# Ada_-_V2_as_built.net
KiCad netlist of a schematic drawn in EasyEDA Pro
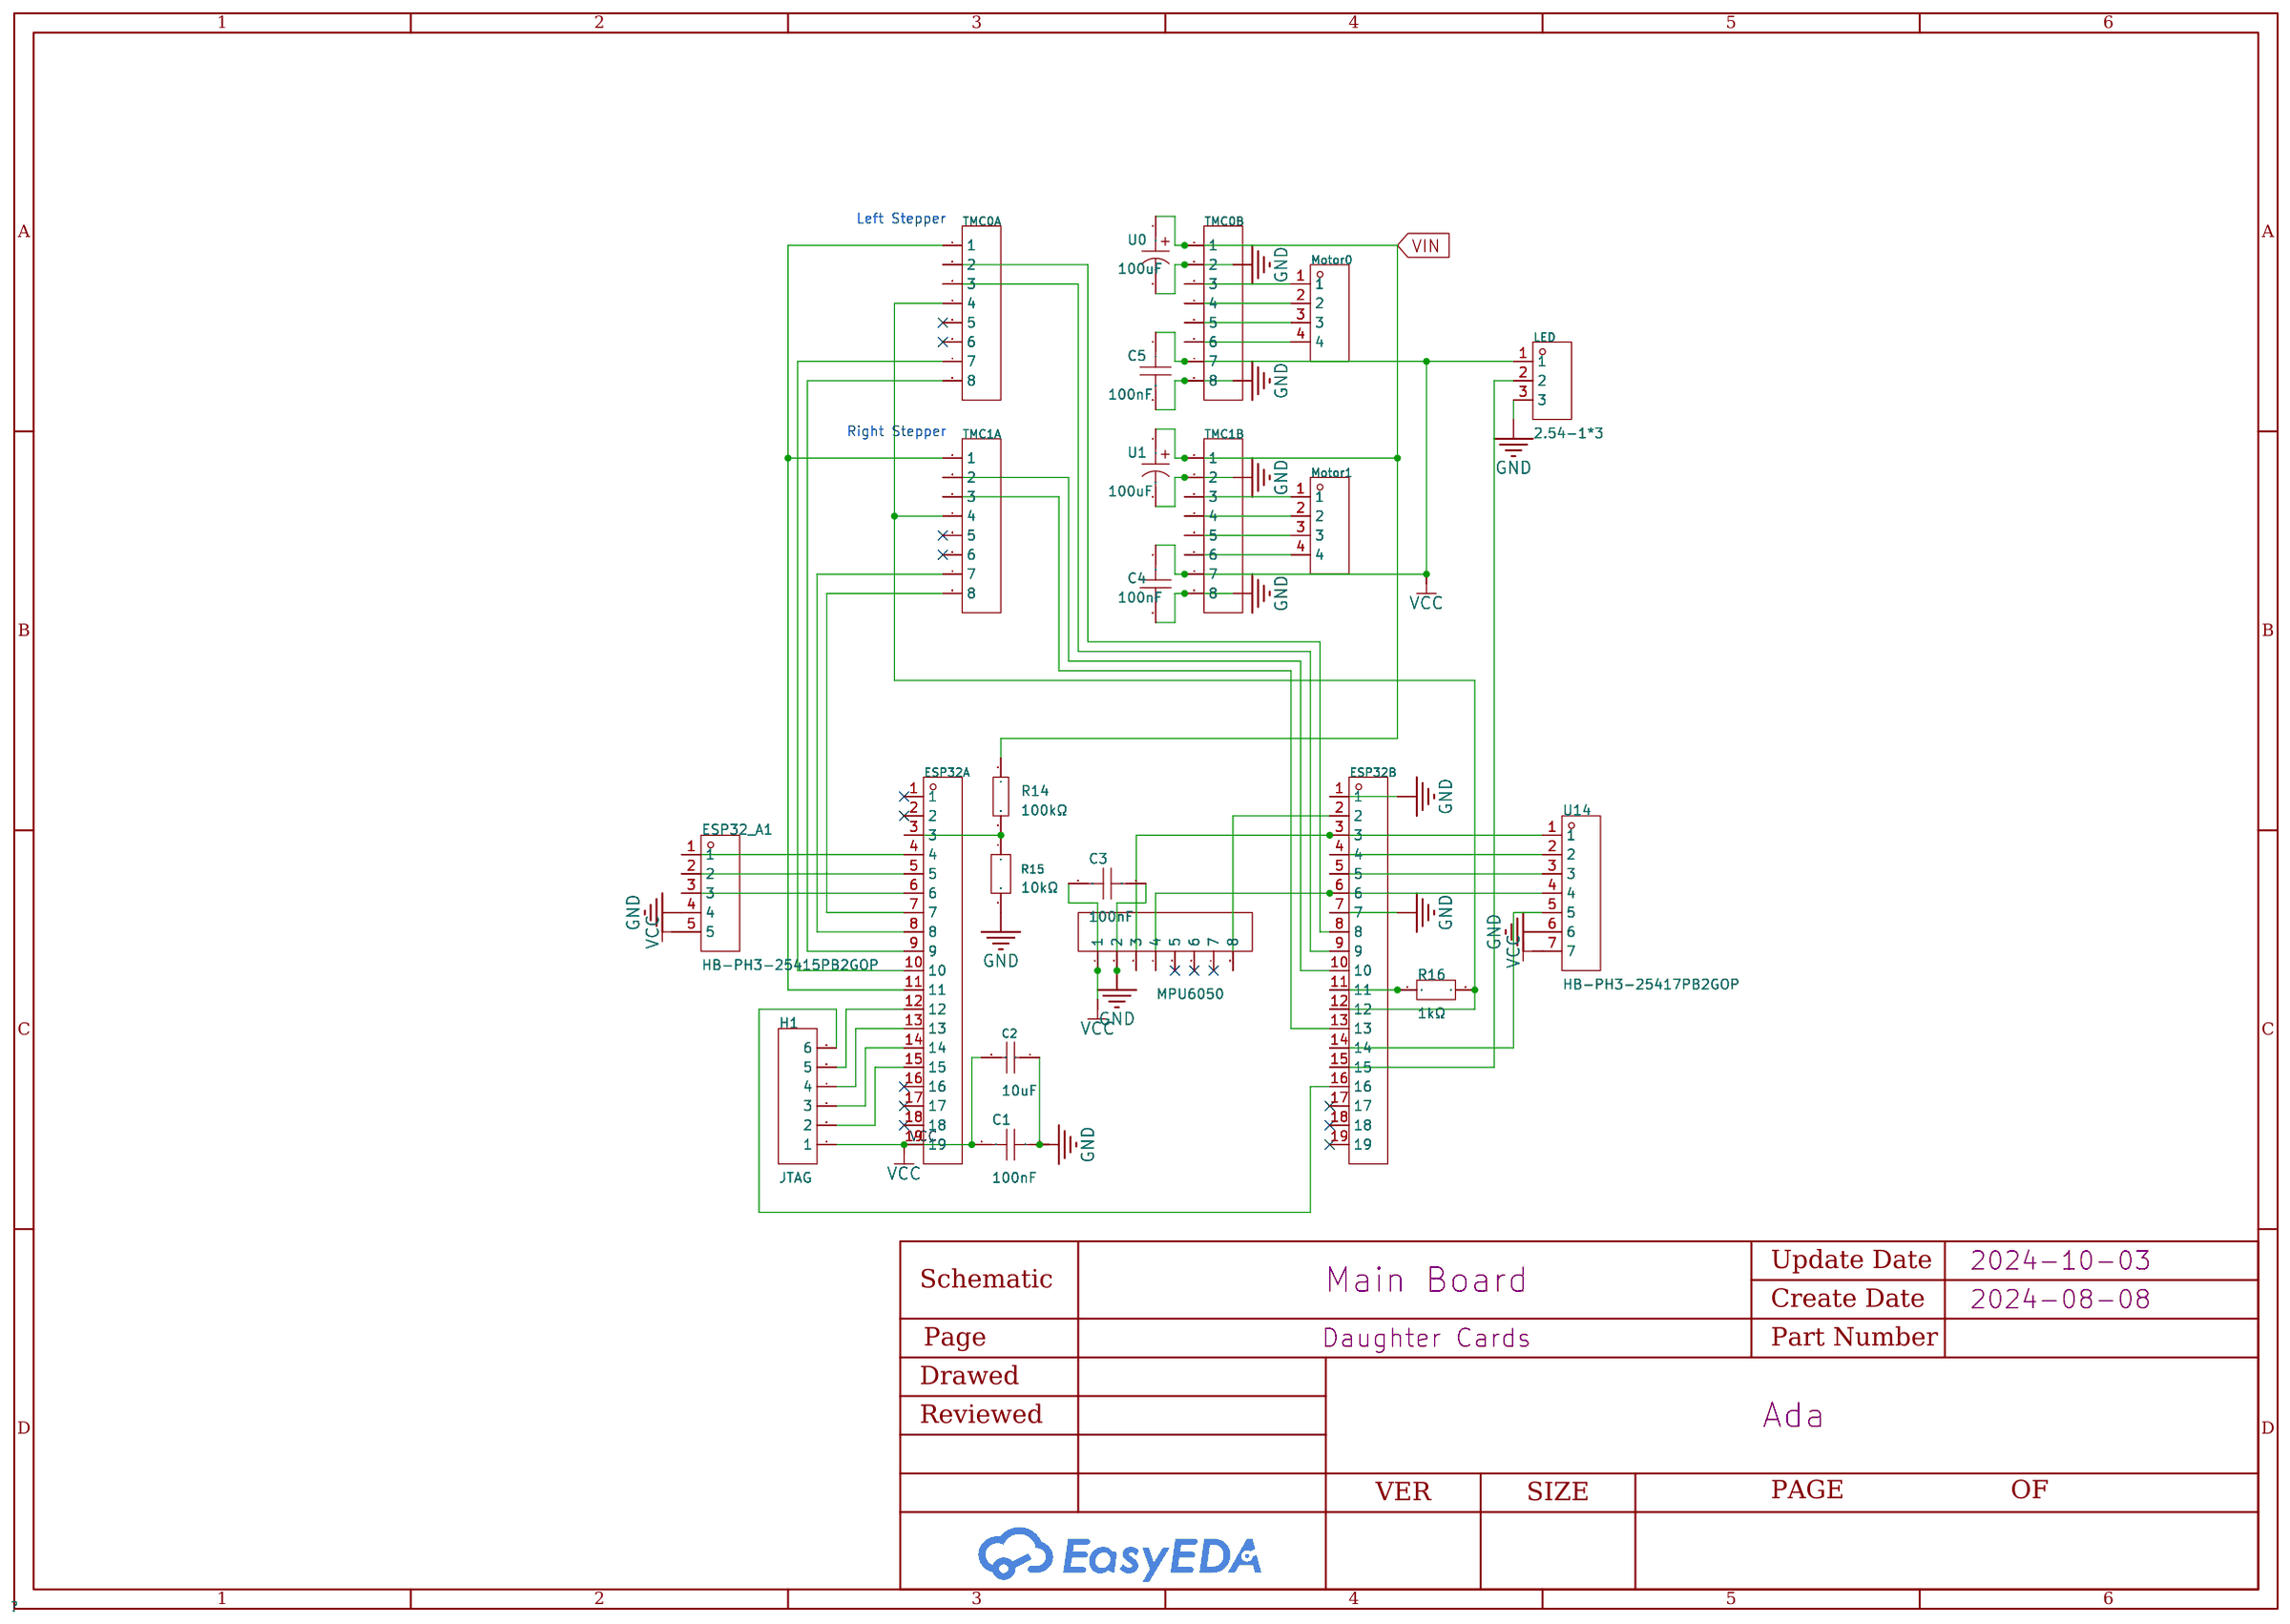
[diagram p0: Daughter Cards]
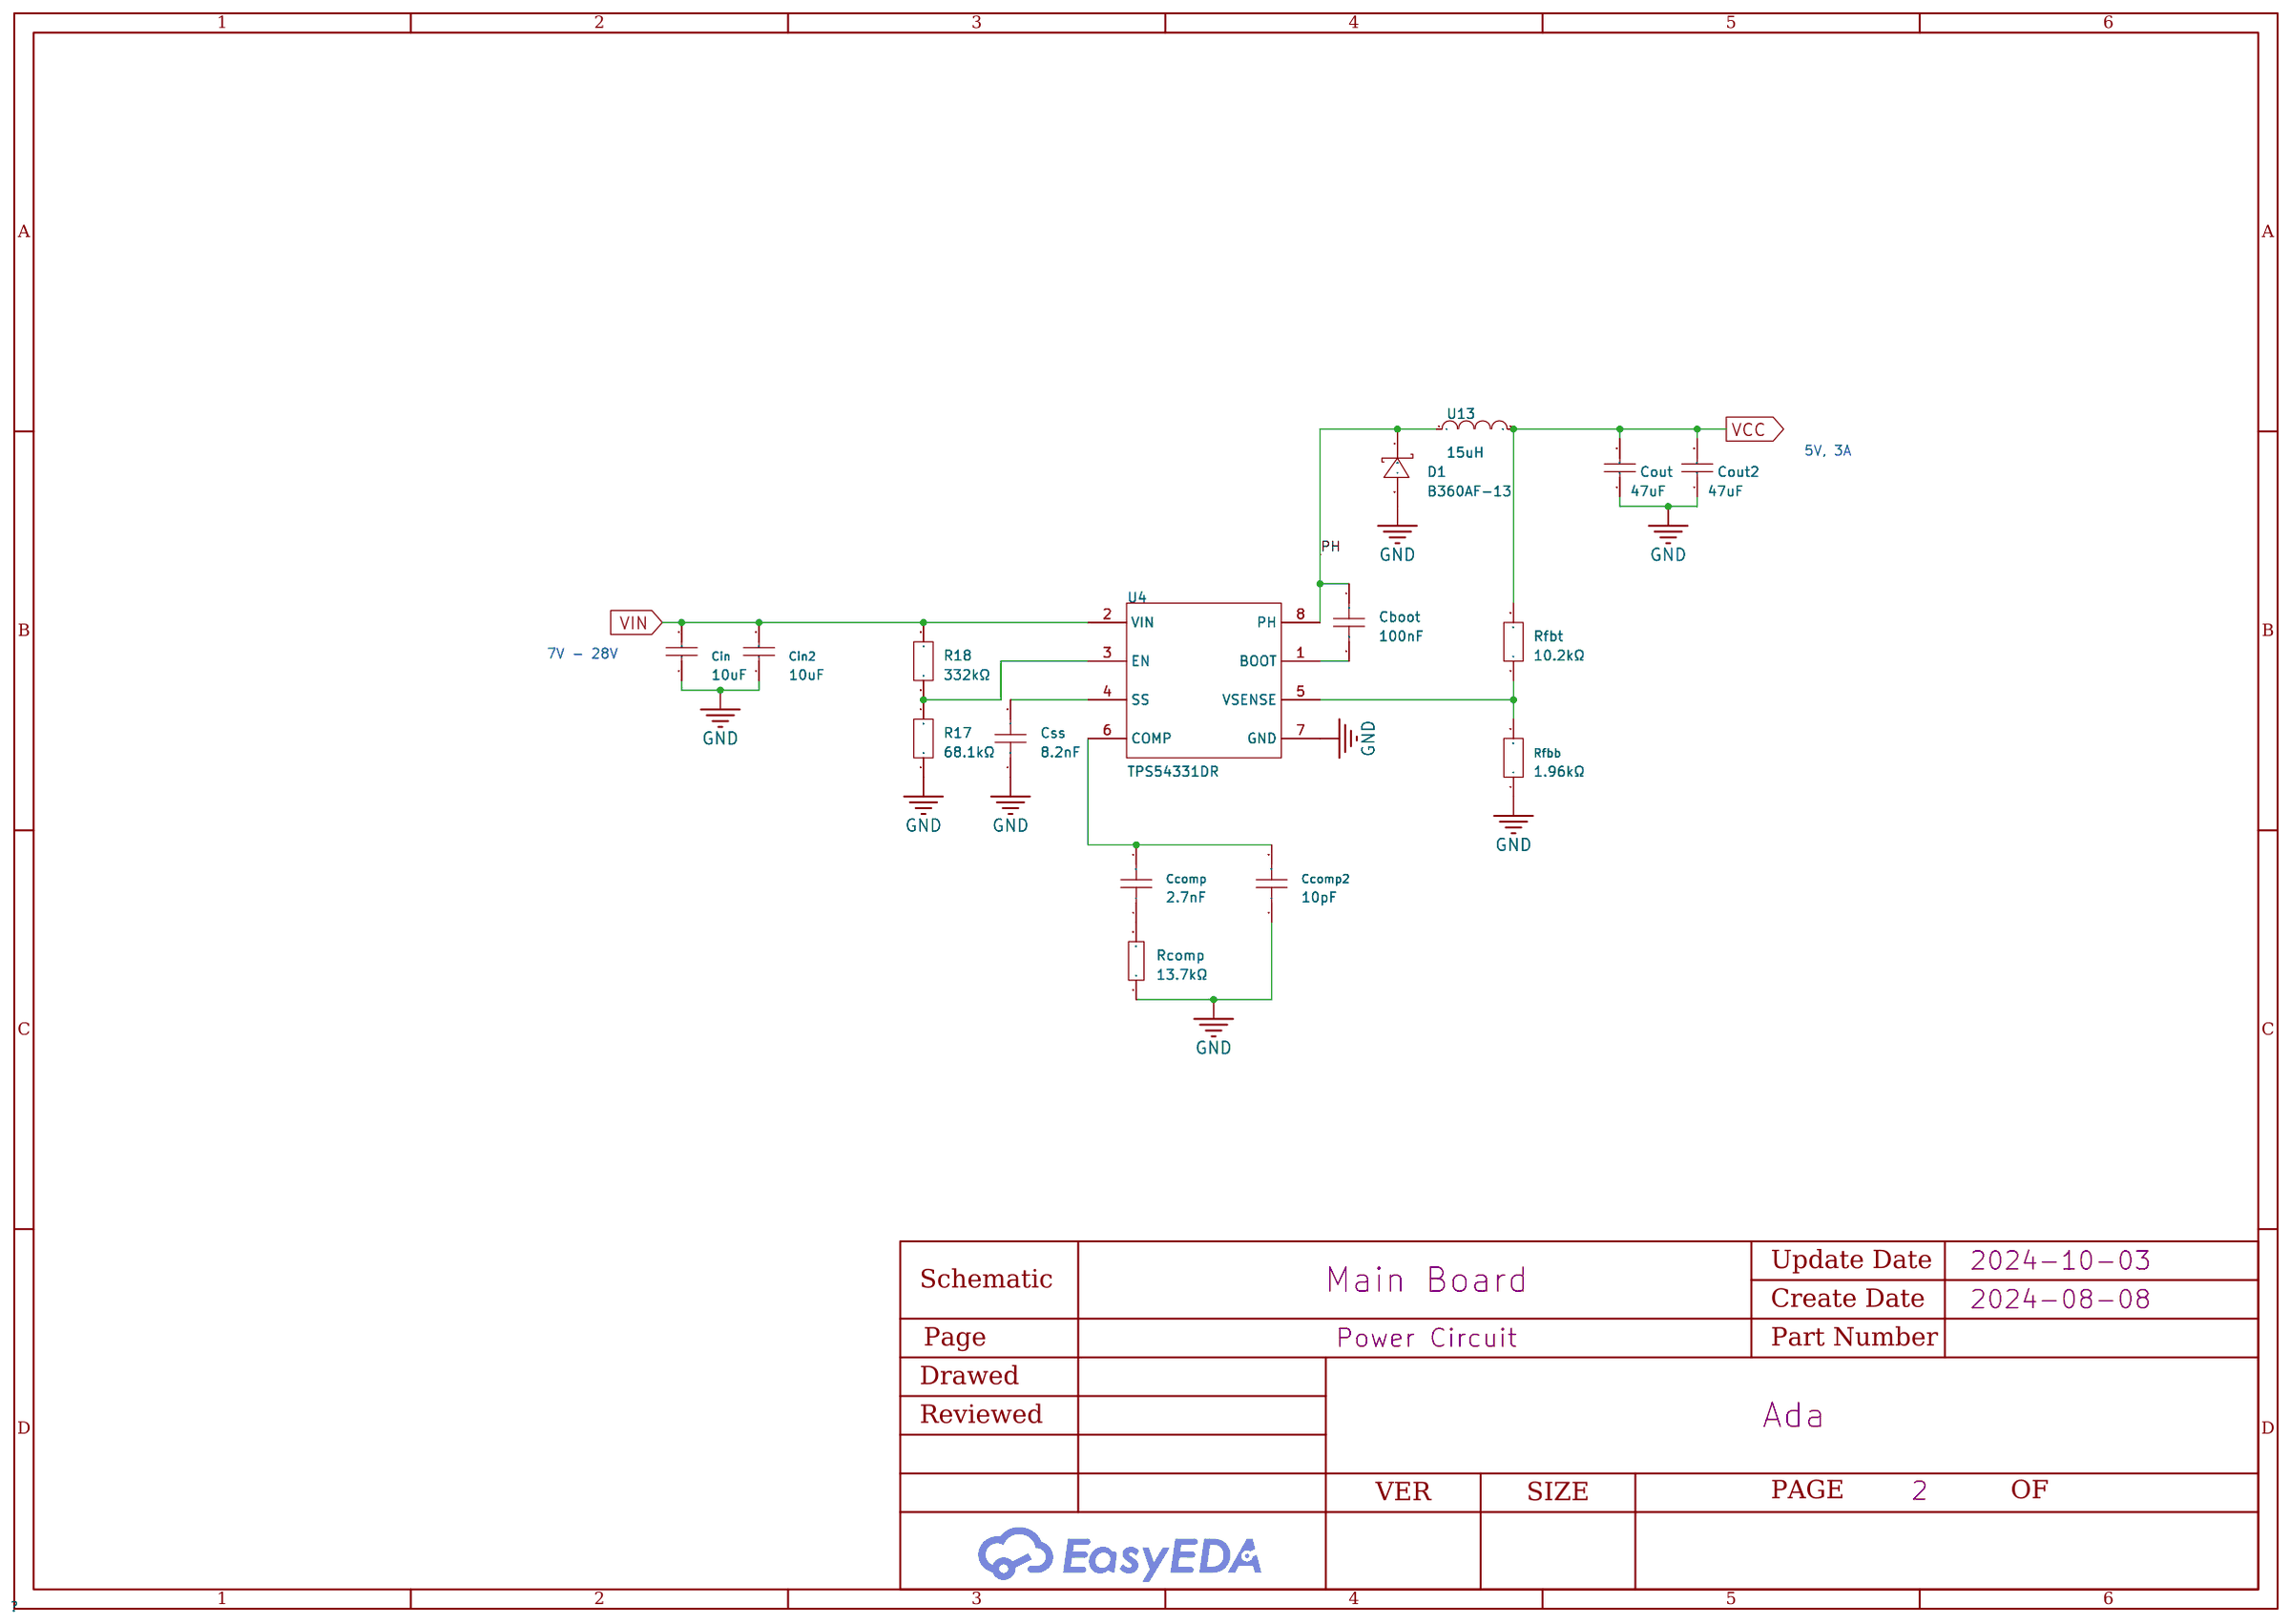
[diagram p1: Power Circuit]

(export (version "E")
  (design (tool "Eeschema 10.0.6"))
  (components
    (comp (ref "C1")
      (value "100nF")
      (footprint "easyedapro:C0201")
      (fields
        (field (name "Manufacturer Part") "CL03A104KQ3NNNC")
        (field (name "Manufacturer") "SAMSUNG(三星)")
      )
      (libsource (lib "easyedapro") (part "CL03A104KQ3NNNC"))
    )
    (comp (ref "C2")
      (value "10uF")
      (footprint "easyedapro:C0402")
      (fields
        (field (name "Manufacturer Part") "CL05A106MQ5NUNC")
        (field (name "Manufacturer") "SAMSUNG(三星)")
      )
      (libsource (lib "easyedapro") (part "CL05A106MQ5NUNC"))
    )
    (comp (ref "C3")
      (value "100nF")
      (footprint "easyedapro:C0201")
      (fields
        (field (name "Manufacturer Part") "CL03A104KQ3NNNC")
        (field (name "Manufacturer") "SAMSUNG(三星)")
      )
      (libsource (lib "easyedapro") (part "CL03A104KQ3NNNC"))
    )
    (comp (ref "C4")
      (value "100nF")
      (footprint "easyedapro:C0201")
      (fields
        (field (name "Manufacturer Part") "CL03A104KQ3NNNC")
        (field (name "Manufacturer") "SAMSUNG(三星)")
      )
      (libsource (lib "easyedapro") (part "CL03A104KQ3NNNC"))
    )
    (comp (ref "C5")
      (value "100nF")
      (footprint "easyedapro:C0201")
      (fields
        (field (name "Manufacturer Part") "CL03A104KQ3NNNC")
        (field (name "Manufacturer") "SAMSUNG(三星)")
      )
      (libsource (lib "easyedapro") (part "CL03A104KQ3NNNC"))
    )
    (comp (ref "ESP32A")
      (value "ESP32")
      (footprint "easyedapro:HDR-TH_19P-P2.54-V-F")
      (fields (field (name "Manufacturer Part") "2.54-1*19P母") (field (name "Manufacturer") "BOOMELE(博穆精密)"))
      (libsource (lib "easyedapro") (part "2.54-1*19P母"))
    )
    (comp (ref "ESP32B")
      (value "2.54-1*19P母")
      (footprint "easyedapro:HDR-TH_19P-P2.54-V-F")
      (fields (field (name "Manufacturer") "BOOMELE(博穆精密)"))
      (libsource (lib "easyedapro") (part "2.54-1*19P母"))
    )
    (comp (ref "ESP32_A1")
      (value "HB-PH3-25415PB2GOP")
      (footprint "easyedapro:HDR-TH_5P-P2.54-V-M")
      (fields (field (name "Manufacturer") "HANBO(汉博)"))
      (libsource (lib "easyedapro") (part "HB-PH3-25415PB2GOP"))
    )
    (comp (ref "H1")
      (value "JTAG")
      (footprint "easyedapro:HDR-TH_6P-P2.54-V-M-1")
      (fields (field (name "Manufacturer Part") "2.54-1x6P直针") (field (name "Manufacturer") "BOOMELE(博穆精密)"))
      (libsource (lib "easyedapro") (part "Header-Male-2.54_1x6"))
    )
    (comp (ref "LED")
      (value "2.54-1*3")
      (footprint "easyedapro:HDR-TH_3P-P2.54-V-M-1")
      (description "Pin Structure:1x3P Pitch:2.54mm Number of Rows:Plugin Number of Pins:3P Contact Plating:Gold")
      (fields (field (name "Manufacturer") "ZHOURI(洲日)"))
      (libsource (lib "easyedapro") (part "2.54-1*3"))
    )
    (comp (ref "Motor0")
      (value "Motor 0")
      (footprint "easyedapro:HDR-TH_4P-P2.54-V-M")
      (fields (field (name "Manufacturer Part") "PZ254V-11-04P") (field (name "Manufacturer") "XFCN(兴飞)"))
      (libsource (lib "easyedapro") (part "PZ254V-11-04P_C2691448"))
    )
    (comp (ref "Motor1")
      (value "Motor 1")
      (footprint "easyedapro:HDR-TH_4P-P2.54-V-M")
      (fields (field (name "Manufacturer Part") "PZ254V-11-04P") (field (name "Manufacturer") "XFCN(兴飞)"))
      (libsource (lib "easyedapro") (part "PZ254V-11-04P_C2691448"))
    )
    (comp (ref "MPU6050")
      (value "MPU6050")
      (footprint "easyedapro:HDR-TH_8P-P2.54-V-F-1")
      (fields (field (name "Manufacturer Part") "2.54-1*8P母环保") (field (name "Manufacturer") "BOOMELE(博穆精密)"))
      (libsource (lib "easyedapro") (part "Header-Female-2.54_1x8"))
    )
    (comp (ref "R14")
      (value "100kΩ")
      (footprint "easyedapro:R0201")
      (fields
        (field (name "Manufacturer Part") "0201WMF1003TEE")
        (field (name "Manufacturer") "UNI-ROYAL(厚声)")
      )
      (libsource (lib "easyedapro") (part "0201WMF1003TEE"))
    )
    (comp (ref "R15")
      (value "10kΩ")
      (footprint "easyedapro:R0201")
      (fields
        (field (name "Manufacturer Part") "0201WMF1002TEE")
        (field (name "Manufacturer") "UNI-ROYAL(厚声)")
      )
      (libsource (lib "easyedapro") (part "0201WMF1002TEE"))
    )
    (comp (ref "R16")
      (value "1kΩ")
      (footprint "easyedapro:R01005")
      (fields
        (field (name "Manufacturer Part") "0105WHJ0102TDE")
        (field (name "Manufacturer") "UNI-ROYAL(厚声)")
      )
      (libsource (lib "easyedapro") (part "0105WHJ0102TDE"))
    )
    (comp (ref "TMC0A")
      (value "TMC0A")
      (footprint "easyedapro:HDR-TH_8P-P2.54-V-F-1")
      (fields (field (name "Manufacturer Part") "2.54-1*8P母环保") (field (name "Manufacturer") "BOOMELE(博穆精密)"))
      (libsource (lib "easyedapro") (part "Header-Female-2.54_1x8"))
    )
    (comp (ref "TMC0B")
      (value "2.54-1*8P母环保")
      (footprint "easyedapro:HDR-TH_8P-P2.54-V-F-1")
      (fields (field (name "Manufacturer") "BOOMELE(博穆精密)"))
      (libsource (lib "easyedapro") (part "Header-Female-2.54_1x8"))
    )
    (comp (ref "TMC1A")
      (value "TMC2209")
      (footprint "easyedapro:HDR-TH_8P-P2.54-V-F-1")
      (fields (field (name "Manufacturer Part") "2.54-1*8P母环保") (field (name "Manufacturer") "BOOMELE(博穆精密)"))
      (libsource (lib "easyedapro") (part "Header-Female-2.54_1x8"))
    )
    (comp (ref "TMC1B")
      (value "2.54-1*8P母环保")
      (footprint "easyedapro:HDR-TH_8P-P2.54-V-F-1")
      (fields (field (name "Manufacturer") "BOOMELE(博穆精密)"))
      (libsource (lib "easyedapro") (part "Header-Female-2.54_1x8"))
    )
    (comp (ref "U0")
      (value "100uF")
      (footprint "easyedapro:CAP-TH_BD6.3-P2.50-D0.5-FD")
      (fields (field (name "Manufacturer Part") "03EC0728") (field (name "Manufacturer") "KNSCHA(科尼盛)"))
      (libsource (lib "easyedapro") (part "03EC0728"))
    )
    (comp (ref "U1")
      (value "100uF")
      (footprint "easyedapro:CAP-TH_BD6.3-P2.50-D0.5-FD")
      (fields (field (name "Manufacturer Part") "03EC0728") (field (name "Manufacturer") "KNSCHA(科尼盛)"))
      (libsource (lib "easyedapro") (part "03EC0728"))
    )
    (comp (ref "U14")
      (value "HB-PH3-25417PB2GOP")
      (footprint "easyedapro:HDR-TH_7P-P2.54-V-M")
      (fields (field (name "Manufacturer") "HANBO(汉博)"))
      (libsource (lib "easyedapro") (part "HB-PH3-25417PB2GOP"))
    )
    (comp (ref "Cboot")
      (value "100nF")
      (footprint "easyedapro:C0201")
      (fields
        (field (name "Manufacturer Part") "CL03A104KQ3NNNC")
        (field (name "Manufacturer") "SAMSUNG(三星)")
      )
      (libsource (lib "easyedapro") (part "CL03A104KQ3NNNC"))
    )
    (comp (ref "Ccomp")
      (value "2.7nF")
      (footprint "easyedapro:C0402")
      (fields
        (field (name "Manufacturer Part") "CC0402KRX7R8BB272")
        (field (name "Manufacturer") "YAGEO(国巨)")
      )
      (libsource (lib "easyedapro") (part "CC0402KRX7R8BB272"))
    )
    (comp (ref "Ccomp2")
      (value "10pF")
      (footprint "easyedapro:C0402")
      (fields (field (name "Manufacturer Part") "0402N100J250CT") (field (name "Manufacturer") "Walsin(华新科)"))
      (libsource (lib "easyedapro") (part "0402N100J250CT"))
    )
    (comp (ref "Cin")
      (value "10uF")
      (footprint "easyedapro:C1206")
      (fields
        (field (name "Manufacturer Part") "CL31A106KAHNNNE")
        (field (name "Manufacturer") "SAMSUNG(三星)")
      )
      (libsource (lib "easyedapro") (part "CL31A106KAHNNNE"))
    )
    (comp (ref "Cin2")
      (value "10uF")
      (footprint "easyedapro:C1206")
      (fields
        (field (name "Manufacturer Part") "CL31A106KAHNNNE")
        (field (name "Manufacturer") "SAMSUNG(三星)")
      )
      (libsource (lib "easyedapro") (part "CL31A106KAHNNNE"))
    )
    (comp (ref "Cout")
      (value "47uF")
      (footprint "easyedapro:C0805")
      (fields
        (field (name "Manufacturer Part") "CL21A476MQYNNNE")
        (field (name "Manufacturer") "SAMSUNG(三星)")
      )
      (libsource (lib "easyedapro") (part "CL21A476MQYNNNE"))
    )
    (comp (ref "Cout2")
      (value "47uF")
      (footprint "easyedapro:C0805")
      (fields
        (field (name "Manufacturer Part") "CL21A476MQYNNNE")
        (field (name "Manufacturer") "SAMSUNG(三星)")
      )
      (libsource (lib "easyedapro") (part "CL21A476MQYNNNE"))
    )
    (comp (ref "Css")
      (value "8.2nF")
      (footprint "easyedapro:C0201")
      (fields (field (name "Manufacturer Part") "C0603X7R822KDTS") (field (name "Manufacturer") "DARFON(达方)"))
      (libsource (lib "easyedapro") (part "C0603X7R822KDTS"))
    )
    (comp (ref "D1")
      (value "B360AF-13")
      (footprint "easyedapro:SMA_L4.4-W2.6-LS5.0-RD")
      (fields (field (name "Manufacturer") "DIODES(美台)"))
      (libsource (lib "easyedapro") (part "B360AF-13"))
    )
    (comp (ref "R17")
      (value "68.1kΩ")
      (footprint "easyedapro:R0201")
      (fields (field (name "Manufacturer Part") "RM02FTN6812") (field (name "Manufacturer") "大毅科技"))
      (libsource (lib "easyedapro") (part "RM02FTN6812"))
    )
    (comp (ref "R18")
      (value "332kΩ")
      (footprint "easyedapro:R0201")
      (fields
        (field (name "Manufacturer Part") "0201WMF3323TEE")
        (field (name "Manufacturer") "UNI-ROYAL(厚声)")
      )
      (libsource (lib "easyedapro") (part "0201WMF3323TEE"))
    )
    (comp (ref "Rcomp")
      (value "13.7kΩ")
      (footprint "easyedapro:R0201")
      (fields (field (name "Manufacturer Part") "RC-01W1372FT") (field (name "Manufacturer") "FH(风华)"))
      (libsource (lib "easyedapro") (part "RC-01W1372FT"))
    )
    (comp (ref "Rfbb")
      (value "1.96kΩ")
      (footprint "easyedapro:R0201")
      (fields
        (field (name "Manufacturer Part") "0201WMF1961TEE")
        (field (name "Manufacturer") "UNI-ROYAL(厚声)")
      )
      (libsource (lib "easyedapro") (part "0201WMF1961TEE"))
    )
    (comp (ref "Rfbt")
      (value "10.2kΩ")
      (footprint "easyedapro:R0201")
      (fields (field (name "Manufacturer Part") "RTT011022FTH") (field (name "Manufacturer") "RALEC(旺诠)"))
      (libsource (lib "easyedapro") (part "RTT011022FTH"))
    )
    (comp (ref "U4")
      (value "TPS54331DR")
      (footprint "easyedapro:SOIC-8_L5.0-W4.0-P1.27-LS6.0-BL")
      (fields (field (name "Manufacturer") "TI(德州仪器)"))
      (libsource (lib "easyedapro") (part "TPS54331DR"))
    )
    (comp (ref "U13")
      (value "15uH")
      (footprint "easyedapro:IND-SMD_L7.2-W6.6_GPSR07X0")
      (description "Inductance: Tolerance:±20% Tolerance:±20% Rated Current: DC Resistance (DCR):98mΩ")
      (fields (field (name "Manufacturer Part") "CYA0630-15UH") (field (name "Manufacturer") "SHOU HAN(首韩)"))
      (libsource (lib "easyedapro") (part "CYA0630-15UH"))
    )
  )
  (nets
    (net (code "1") (name "GND") (class "Default")
      (node (ref "C1") (pin "2") (pinfunction "2_2") (pintype "unspecified"))
      (node (ref "C2") (pin "1") (pinfunction "1_1") (pintype "input"))
      (node (ref "C3") (pin "2") (pinfunction "2_2") (pintype "unspecified"))
      (node (ref "C4") (pin "2") (pinfunction "2_2") (pintype "unspecified"))
      (node (ref "C5") (pin "2") (pinfunction "2_2") (pintype "unspecified"))
      (node (ref "Ccomp2") (pin "1") (pinfunction "1_1") (pintype "input"))
      (node (ref "Cin") (pin "1") (pinfunction "1_1") (pintype "input"))
      (node (ref "Cin2") (pin "1") (pinfunction "1_1") (pintype "input"))
      (node (ref "Cout") (pin "1") (pinfunction "1_1") (pintype "input"))
      (node (ref "Cout2") (pin "1") (pinfunction "1_1") (pintype "input"))
      (node (ref "Css") (pin "1") (pinfunction "1_1") (pintype "unspecified"))
      (node (ref "D1") (pin "2") (pinfunction "A_2") (pintype "unspecified"))
      (node (ref "ESP32B") (pin "1") (pinfunction "1_1") (pintype "input"))
      (node (ref "ESP32B") (pin "7") (pinfunction "7_7") (pintype "input"))
      (node (ref "ESP32_A1") (pin "4") (pinfunction "4_4") (pintype "unspecified"))
      (node (ref "LED") (pin "3") (pinfunction "3_3") (pintype "input"))
      (node (ref "MPU6050") (pin "2") (pinfunction "2_2") (pintype "input"))
      (node (ref "R15") (pin "2") (pinfunction "2_2") (pintype "input"))
      (node (ref "R17") (pin "1") (pinfunction "1_1") (pintype "unspecified"))
      (node (ref "Rcomp") (pin "1") (pinfunction "1_1") (pintype "unspecified"))
      (node (ref "Rfbb") (pin "1") (pinfunction "1_1") (pintype "input"))
      (node (ref "TMC0B") (pin "2") (pinfunction "2_2") (pintype "input"))
      (node (ref "TMC0B") (pin "8") (pinfunction "8_8") (pintype "input"))
      (node (ref "TMC1B") (pin "2") (pinfunction "2_2") (pintype "input"))
      (node (ref "TMC1B") (pin "8") (pinfunction "8_8") (pintype "input"))
      (node (ref "U0") (pin "2") (pinfunction "2_2") (pintype "input"))
      (node (ref "U1") (pin "2") (pinfunction "2_2") (pintype "input"))
      (node (ref "U14") (pin "6") (pinfunction "6_6") (pintype "unspecified"))
      (node (ref "U4") (pin "7") (pinfunction "GND_7") (pintype "unspecified"))
    )
    (net (code "2") (name "Net-(Ccomp-Pad1)") (class "Default")
      (node (ref "Ccomp") (pin "1") (pinfunction "1_1") (pintype "input"))
      (node (ref "Rcomp") (pin "2") (pinfunction "2_2") (pintype "unspecified"))
    )
    (net (code "3") (name "Net-(ESP32A-Pad3)") (class "Default")
      (node (ref "ESP32A") (pin "3") (pinfunction "3_3") (pintype "input"))
      (node (ref "R14") (pin "2") (pinfunction "2_2") (pintype "unspecified"))
      (node (ref "R15") (pin "1") (pinfunction "1_1") (pintype "input"))
    )
    (net (code "4") (name "Net-(ESP32A-Pad4)") (class "Default")
      (node (ref "ESP32A") (pin "4") (pinfunction "4_4") (pintype "input"))
      (node (ref "ESP32_A1") (pin "1") (pinfunction "1_1") (pintype "unspecified"))
    )
    (net (code "5") (name "Net-(ESP32A-Pad5)") (class "Default")
      (node (ref "ESP32A") (pin "5") (pinfunction "5_5") (pintype "input"))
      (node (ref "ESP32_A1") (pin "2") (pinfunction "2_2") (pintype "unspecified"))
    )
    (net (code "6") (name "Net-(ESP32A-Pad6)") (class "Default")
      (node (ref "ESP32A") (pin "6") (pinfunction "6_6") (pintype "input"))
      (node (ref "ESP32_A1") (pin "3") (pinfunction "3_3") (pintype "unspecified"))
    )
    (net (code "7") (name "Net-(ESP32A-Pad7)") (class "Default")
      (node (ref "ESP32A") (pin "7") (pinfunction "7_7") (pintype "input"))
      (node (ref "TMC1A") (pin "8") (pinfunction "8_8") (pintype "input"))
    )
    (net (code "8") (name "Net-(ESP32A-Pad8)") (class "Default")
      (node (ref "ESP32A") (pin "8") (pinfunction "8_8") (pintype "input"))
      (node (ref "TMC1A") (pin "7") (pinfunction "7_7") (pintype "input"))
    )
    (net (code "9") (name "Net-(ESP32A-Pad9)") (class "Default")
      (node (ref "ESP32A") (pin "9") (pinfunction "9_9") (pintype "input"))
      (node (ref "TMC0A") (pin "8") (pinfunction "8_8") (pintype "input"))
    )
    (net (code "10") (name "Net-(ESP32A-Pad10)") (class "Default")
      (node (ref "ESP32A") (pin "10") (pinfunction "10_10") (pintype "input"))
      (node (ref "TMC0A") (pin "7") (pinfunction "7_7") (pintype "input"))
    )
    (net (code "11") (name "Net-(ESP32A-Pad11)") (class "Default")
      (node (ref "ESP32A") (pin "11") (pinfunction "11_11") (pintype "input"))
      (node (ref "TMC0A") (pin "1") (pinfunction "1_1") (pintype "input"))
      (node (ref "TMC1A") (pin "1") (pinfunction "1_1") (pintype "input"))
    )
    (net (code "12") (name "Net-(ESP32A-Pad12)") (class "Default")
      (node (ref "ESP32A") (pin "12") (pinfunction "12_12") (pintype "input"))
      (node (ref "H1") (pin "5") (pinfunction "5_5") (pintype "input"))
    )
    (net (code "13") (name "Net-(ESP32A-Pad13)") (class "Default")
      (node (ref "ESP32A") (pin "13") (pinfunction "13_13") (pintype "input"))
      (node (ref "H1") (pin "4") (pinfunction "4_4") (pintype "input"))
    )
    (net (code "14") (name "Net-(ESP32A-Pad14)") (class "Default")
      (node (ref "ESP32A") (pin "14") (pinfunction "14_14") (pintype "input"))
      (node (ref "H1") (pin "3") (pinfunction "3_3") (pintype "input"))
    )
    (net (code "15") (name "Net-(ESP32A-Pad15)") (class "Default")
      (node (ref "ESP32A") (pin "15") (pinfunction "15_15") (pintype "input"))
      (node (ref "H1") (pin "2") (pinfunction "2_2") (pintype "input"))
    )
    (net (code "16") (name "Net-(ESP32B-Pad2)") (class "Default")
      (node (ref "ESP32B") (pin "2") (pinfunction "2_2") (pintype "input"))
      (node (ref "MPU6050") (pin "8") (pinfunction "8_8") (pintype "input"))
    )
    (net (code "17") (name "Net-(ESP32B-Pad3)") (class "Default")
      (node (ref "ESP32B") (pin "3") (pinfunction "3_3") (pintype "input"))
      (node (ref "MPU6050") (pin "3") (pinfunction "3_3") (pintype "input"))
      (node (ref "U14") (pin "1") (pinfunction "1_1") (pintype "unspecified"))
    )
    (net (code "18") (name "Net-(ESP32B-Pad4)") (class "Default")
      (node (ref "ESP32B") (pin "4") (pinfunction "4_4") (pintype "input"))
      (node (ref "U14") (pin "2") (pinfunction "2_2") (pintype "unspecified"))
    )
    (net (code "19") (name "Net-(ESP32B-Pad5)") (class "Default")
      (node (ref "ESP32B") (pin "5") (pinfunction "5_5") (pintype "input"))
      (node (ref "U14") (pin "3") (pinfunction "3_3") (pintype "unspecified"))
    )
    (net (code "20") (name "Net-(ESP32B-Pad6)") (class "Default")
      (node (ref "ESP32B") (pin "6") (pinfunction "6_6") (pintype "input"))
      (node (ref "MPU6050") (pin "4") (pinfunction "4_4") (pintype "input"))
      (node (ref "U14") (pin "4") (pinfunction "4_4") (pintype "unspecified"))
    )
    (net (code "21") (name "Net-(ESP32B-Pad8)") (class "Default")
      (node (ref "ESP32B") (pin "8") (pinfunction "8_8") (pintype "input"))
      (node (ref "TMC0A") (pin "2") (pinfunction "2_2") (pintype "input"))
    )
    (net (code "22") (name "Net-(ESP32B-Pad9)") (class "Default")
      (node (ref "ESP32B") (pin "9") (pinfunction "9_9") (pintype "input"))
      (node (ref "TMC0A") (pin "3") (pinfunction "3_3") (pintype "input"))
    )
    (net (code "23") (name "Net-(ESP32B-Pad10)") (class "Default")
      (node (ref "ESP32B") (pin "10") (pinfunction "10_10") (pintype "input"))
      (node (ref "TMC1A") (pin "2") (pinfunction "2_2") (pintype "input"))
    )
    (net (code "24") (name "Net-(ESP32B-Pad11)") (class "Default")
      (node (ref "ESP32B") (pin "11") (pinfunction "11_11") (pintype "input"))
      (node (ref "R16") (pin "1") (pinfunction "1_1") (pintype "unspecified"))
    )
    (net (code "25") (name "Net-(ESP32B-Pad12)") (class "Default")
      (node (ref "ESP32B") (pin "12") (pinfunction "12_12") (pintype "input"))
      (node (ref "R16") (pin "2") (pinfunction "2_2") (pintype "unspecified"))
      (node (ref "TMC0A") (pin "4") (pinfunction "4_4") (pintype "input"))
      (node (ref "TMC1A") (pin "4") (pinfunction "4_4") (pintype "input"))
    )
    (net (code "26") (name "Net-(ESP32B-Pad13)") (class "Default")
      (node (ref "ESP32B") (pin "13") (pinfunction "13_13") (pintype "input"))
      (node (ref "TMC1A") (pin "3") (pinfunction "3_3") (pintype "input"))
    )
    (net (code "27") (name "Net-(ESP32B-Pad14)") (class "Default")
      (node (ref "ESP32B") (pin "14") (pinfunction "14_14") (pintype "input"))
      (node (ref "U14") (pin "5") (pinfunction "5_5") (pintype "unspecified"))
    )
    (net (code "28") (name "Net-(ESP32B-Pad15)") (class "Default")
      (node (ref "ESP32B") (pin "15") (pinfunction "15_15") (pintype "input"))
      (node (ref "LED") (pin "2") (pinfunction "2_2") (pintype "input"))
    )
    (net (code "29") (name "Net-(ESP32B-Pad16)") (class "Default")
      (node (ref "ESP32B") (pin "16") (pinfunction "16_16") (pintype "input"))
      (node (ref "H1") (pin "6") (pinfunction "6_6") (pintype "input"))
    )
    (net (code "30") (name "Net-(Motor0-Pad1)") (class "Default")
      (node (ref "Motor0") (pin "1") (pinfunction "1_1") (pintype "input"))
      (node (ref "TMC0B") (pin "3") (pinfunction "3_3") (pintype "input"))
    )
    (net (code "31") (name "Net-(Motor0-Pad2)") (class "Default")
      (node (ref "Motor0") (pin "2") (pinfunction "2_2") (pintype "input"))
      (node (ref "TMC0B") (pin "4") (pinfunction "4_4") (pintype "input"))
    )
    (net (code "32") (name "Net-(Motor0-Pad3)") (class "Default")
      (node (ref "Motor0") (pin "3") (pinfunction "3_3") (pintype "input"))
      (node (ref "TMC0B") (pin "5") (pinfunction "5_5") (pintype "input"))
    )
    (net (code "33") (name "Net-(Motor0-Pad4)") (class "Default")
      (node (ref "Motor0") (pin "4") (pinfunction "4_4") (pintype "input"))
      (node (ref "TMC0B") (pin "6") (pinfunction "6_6") (pintype "input"))
    )
    (net (code "34") (name "Net-(Motor1-Pad1)") (class "Default")
      (node (ref "Motor1") (pin "1") (pinfunction "1_1") (pintype "input"))
      (node (ref "TMC1B") (pin "3") (pinfunction "3_3") (pintype "input"))
    )
    (net (code "35") (name "Net-(Motor1-Pad2)") (class "Default")
      (node (ref "Motor1") (pin "2") (pinfunction "2_2") (pintype "input"))
      (node (ref "TMC1B") (pin "4") (pinfunction "4_4") (pintype "input"))
    )
    (net (code "36") (name "Net-(Motor1-Pad3)") (class "Default")
      (node (ref "Motor1") (pin "3") (pinfunction "3_3") (pintype "input"))
      (node (ref "TMC1B") (pin "5") (pinfunction "5_5") (pintype "input"))
    )
    (net (code "37") (name "Net-(Motor1-Pad4)") (class "Default")
      (node (ref "Motor1") (pin "4") (pinfunction "4_4") (pintype "input"))
      (node (ref "TMC1B") (pin "6") (pinfunction "6_6") (pintype "input"))
    )
    (net (code "38") (name "Net-(U4-BOOT)") (class "Default")
      (node (ref "Cboot") (pin "2") (pinfunction "2_2") (pintype "unspecified"))
      (node (ref "U4") (pin "1") (pinfunction "BOOT_1") (pintype "unspecified"))
    )
    (net (code "39") (name "Net-(U4-COMP)") (class "Default")
      (node (ref "Ccomp") (pin "2") (pinfunction "2_2") (pintype "input"))
      (node (ref "Ccomp2") (pin "2") (pinfunction "2_2") (pintype "input"))
      (node (ref "U4") (pin "6") (pinfunction "COMP_6") (pintype "unspecified"))
    )
    (net (code "40") (name "Net-(U4-EN)") (class "Default")
      (node (ref "R17") (pin "2") (pinfunction "2_2") (pintype "unspecified"))
      (node (ref "R18") (pin "1") (pinfunction "1_1") (pintype "unspecified"))
      (node (ref "U4") (pin "3") (pinfunction "EN_3") (pintype "unspecified"))
    )
    (net (code "41") (name "Net-(U4-SS)") (class "Default")
      (node (ref "Css") (pin "2") (pinfunction "2_2") (pintype "unspecified"))
      (node (ref "U4") (pin "4") (pinfunction "SS_4") (pintype "unspecified"))
    )
    (net (code "42") (name "Net-(U4-VSENSE)") (class "Default")
      (node (ref "Rfbb") (pin "2") (pinfunction "2_2") (pintype "input"))
      (node (ref "Rfbt") (pin "1") (pinfunction "1_1") (pintype "unspecified"))
      (node (ref "U4") (pin "5") (pinfunction "VSENSE_5") (pintype "unspecified"))
    )
    (net (code "43") (name "PH") (class "Default")
      (node (ref "Cboot") (pin "1") (pinfunction "1_1") (pintype "unspecified"))
      (node (ref "D1") (pin "1") (pinfunction "C_1") (pintype "unspecified"))
      (node (ref "U13") (pin "1") (pinfunction "1_1") (pintype "unspecified"))
      (node (ref "U4") (pin "8") (pinfunction "PH_8") (pintype "unspecified"))
    )
    (net (code "44") (name "VCC") (class "Default")
      (node (ref "C1") (pin "1") (pinfunction "1_1") (pintype "unspecified"))
      (node (ref "C2") (pin "2") (pinfunction "2_2") (pintype "input"))
      (node (ref "C3") (pin "1") (pinfunction "1_1") (pintype "unspecified"))
      (node (ref "C4") (pin "1") (pinfunction "1_1") (pintype "unspecified"))
      (node (ref "C5") (pin "1") (pinfunction "1_1") (pintype "unspecified"))
      (node (ref "Cout") (pin "2") (pinfunction "2_2") (pintype "input"))
      (node (ref "Cout2") (pin "2") (pinfunction "2_2") (pintype "input"))
      (node (ref "ESP32A") (pin "19") (pinfunction "19_19") (pintype "input"))
      (node (ref "ESP32_A1") (pin "5") (pinfunction "5_5") (pintype "unspecified"))
      (node (ref "H1") (pin "1") (pinfunction "1_1") (pintype "input"))
      (node (ref "LED") (pin "1") (pinfunction "1_1") (pintype "input"))
      (node (ref "MPU6050") (pin "1") (pinfunction "1_1") (pintype "input"))
      (node (ref "Rfbt") (pin "2") (pinfunction "2_2") (pintype "unspecified"))
      (node (ref "TMC0B") (pin "7") (pinfunction "7_7") (pintype "input"))
      (node (ref "TMC1B") (pin "7") (pinfunction "7_7") (pintype "input"))
      (node (ref "U13") (pin "2") (pinfunction "2_2") (pintype "unspecified"))
      (node (ref "U14") (pin "7") (pinfunction "7_7") (pintype "unspecified"))
    )
    (net (code "45") (name "VIN") (class "Default")
      (node (ref "Cin") (pin "2") (pinfunction "2_2") (pintype "input"))
      (node (ref "Cin2") (pin "2") (pinfunction "2_2") (pintype "input"))
      (node (ref "R14") (pin "1") (pinfunction "1_1") (pintype "unspecified"))
      (node (ref "R18") (pin "2") (pinfunction "2_2") (pintype "unspecified"))
      (node (ref "TMC0B") (pin "1") (pinfunction "1_1") (pintype "input"))
      (node (ref "TMC1B") (pin "1") (pinfunction "1_1") (pintype "input"))
      (node (ref "U0") (pin "1") (pinfunction "1_1") (pintype "input"))
      (node (ref "U1") (pin "1") (pinfunction "1_1") (pintype "input"))
      (node (ref "U4") (pin "2") (pinfunction "VIN_2") (pintype "unspecified"))
    )
    (net (code "46") (name "unconnected-(ESP32A-Pad1)") (class "Default")
      (node (ref "ESP32A") (pin "1") (pinfunction "1_1") (pintype "input+no_connect"))
    )
    (net (code "47") (name "unconnected-(ESP32A-Pad2)") (class "Default")
      (node (ref "ESP32A") (pin "2") (pinfunction "2_2") (pintype "input+no_connect"))
    )
    (net (code "48") (name "unconnected-(ESP32A-Pad16)") (class "Default")
      (node (ref "ESP32A") (pin "16") (pinfunction "16_16") (pintype "input+no_connect"))
    )
    (net (code "49") (name "unconnected-(ESP32A-Pad17)") (class "Default")
      (node (ref "ESP32A") (pin "17") (pinfunction "17_17") (pintype "input+no_connect"))
    )
    (net (code "50") (name "unconnected-(ESP32A-Pad18)") (class "Default")
      (node (ref "ESP32A") (pin "18") (pinfunction "18_18") (pintype "input+no_connect"))
    )
    (net (code "51") (name "unconnected-(ESP32B-Pad17)") (class "Default")
      (node (ref "ESP32B") (pin "17") (pinfunction "17_17") (pintype "input+no_connect"))
    )
    (net (code "52") (name "unconnected-(ESP32B-Pad18)") (class "Default")
      (node (ref "ESP32B") (pin "18") (pinfunction "18_18") (pintype "input+no_connect"))
    )
    (net (code "53") (name "unconnected-(ESP32B-Pad19)") (class "Default")
      (node (ref "ESP32B") (pin "19") (pinfunction "19_19") (pintype "input+no_connect"))
    )
    (net (code "54") (name "unconnected-(MPU6050-Pad5)") (class "Default")
      (node (ref "MPU6050") (pin "5") (pinfunction "5_5") (pintype "input+no_connect"))
    )
    (net (code "55") (name "unconnected-(MPU6050-Pad6)") (class "Default")
      (node (ref "MPU6050") (pin "6") (pinfunction "6_6") (pintype "input+no_connect"))
    )
    (net (code "56") (name "unconnected-(MPU6050-Pad7)") (class "Default")
      (node (ref "MPU6050") (pin "7") (pinfunction "7_7") (pintype "input+no_connect"))
    )
    (net (code "57") (name "unconnected-(TMC0A-Pad5)") (class "Default")
      (node (ref "TMC0A") (pin "5") (pinfunction "5_5") (pintype "input+no_connect"))
    )
    (net (code "58") (name "unconnected-(TMC0A-Pad6)") (class "Default")
      (node (ref "TMC0A") (pin "6") (pinfunction "6_6") (pintype "input+no_connect"))
    )
    (net (code "59") (name "unconnected-(TMC1A-Pad5)") (class "Default")
      (node (ref "TMC1A") (pin "5") (pinfunction "5_5") (pintype "input+no_connect"))
    )
    (net (code "60") (name "unconnected-(TMC1A-Pad6)") (class "Default")
      (node (ref "TMC1A") (pin "6") (pinfunction "6_6") (pintype "input+no_connect"))
    )
  )
)
